# led_12led.net
KiCad netlist of a schematic drawn in EAGLE
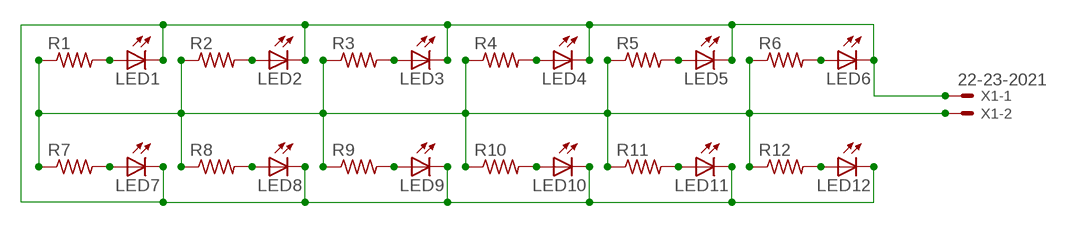
[diagram p0: schematic, sheet 1]

(export (version "E")
  (design (tool "Eeschema 10.0.6"))
  (components
    (comp (ref "LED1")
      (value "LED3MM")
      (footprint "eagle-import:LED3MM")
      (libsource (lib "eagle-import") (part "LED3MM"))
    )
    (comp (ref "LED2")
      (value "LED3MM")
      (footprint "eagle-import:LED3MM")
      (libsource (lib "eagle-import") (part "LED3MM"))
    )
    (comp (ref "LED3")
      (value "LED3MM")
      (footprint "eagle-import:LED3MM")
      (libsource (lib "eagle-import") (part "LED3MM"))
    )
    (comp (ref "LED4")
      (value "LED3MM")
      (footprint "eagle-import:LED3MM")
      (libsource (lib "eagle-import") (part "LED3MM"))
    )
    (comp (ref "LED5")
      (value "LED3MM")
      (footprint "eagle-import:LED3MM")
      (libsource (lib "eagle-import") (part "LED3MM"))
    )
    (comp (ref "LED6")
      (value "LED3MM")
      (footprint "eagle-import:LED3MM")
      (libsource (lib "eagle-import") (part "LED3MM"))
    )
    (comp (ref "LED7")
      (value "LED3MM")
      (footprint "eagle-import:LED3MM")
      (libsource (lib "eagle-import") (part "LED3MM"))
    )
    (comp (ref "LED8")
      (value "LED3MM")
      (footprint "eagle-import:LED3MM")
      (libsource (lib "eagle-import") (part "LED3MM"))
    )
    (comp (ref "LED9")
      (value "LED3MM")
      (footprint "eagle-import:LED3MM")
      (libsource (lib "eagle-import") (part "LED3MM"))
    )
    (comp (ref "LED10")
      (value "LED3MM")
      (footprint "eagle-import:LED3MM")
      (libsource (lib "eagle-import") (part "LED3MM"))
    )
    (comp (ref "LED11")
      (value "LED3MM")
      (footprint "eagle-import:LED3MM")
      (libsource (lib "eagle-import") (part "LED3MM"))
    )
    (comp (ref "LED12")
      (value "LED3MM")
      (footprint "eagle-import:LED3MM")
      (libsource (lib "eagle-import") (part "LED3MM"))
    )
    (comp (ref "R1")
      (value "R-US_0309/12")
      (footprint "eagle-import:0309_12")
      (libsource (lib "eagle-import") (part "R-US_0309/12"))
    )
    (comp (ref "R2")
      (value "R-US_0309/12")
      (footprint "eagle-import:0309_12")
      (libsource (lib "eagle-import") (part "R-US_0309/12"))
    )
    (comp (ref "R3")
      (value "R-US_0309/12")
      (footprint "eagle-import:0309_12")
      (libsource (lib "eagle-import") (part "R-US_0309/12"))
    )
    (comp (ref "R4")
      (value "R-US_0309/12")
      (footprint "eagle-import:0309_12")
      (libsource (lib "eagle-import") (part "R-US_0309/12"))
    )
    (comp (ref "R5")
      (value "R-US_0309/12")
      (footprint "eagle-import:0309_12")
      (libsource (lib "eagle-import") (part "R-US_0309/12"))
    )
    (comp (ref "R6")
      (value "R-US_0309/12")
      (footprint "eagle-import:0309_12")
      (libsource (lib "eagle-import") (part "R-US_0309/12"))
    )
    (comp (ref "R7")
      (value "R-US_0309/12")
      (footprint "eagle-import:0309_12")
      (libsource (lib "eagle-import") (part "R-US_0309/12"))
    )
    (comp (ref "R8")
      (value "R-US_0309/12")
      (footprint "eagle-import:0309_12")
      (libsource (lib "eagle-import") (part "R-US_0309/12"))
    )
    (comp (ref "R9")
      (value "R-US_0309/12")
      (footprint "eagle-import:0309_12")
      (libsource (lib "eagle-import") (part "R-US_0309/12"))
    )
    (comp (ref "R10")
      (value "R-US_0309/12")
      (footprint "eagle-import:0309_12")
      (libsource (lib "eagle-import") (part "R-US_0309/12"))
    )
    (comp (ref "R11")
      (value "R-US_0309/12")
      (footprint "eagle-import:0309_12")
      (libsource (lib "eagle-import") (part "R-US_0309/12"))
    )
    (comp (ref "R12")
      (value "R-US_0309/12")
      (footprint "eagle-import:0309_12")
      (libsource (lib "eagle-import") (part "R-US_0309/12"))
    )
    (comp (ref "X1")
      (value "22-23-2021")
      (footprint "eagle-import:22-23-2021")
      (fields (field (name "MF") "MOLEX"))
      (libsource (lib "eagle-import") (part "22-23-2021"))
    )
  )
  (nets
    (net (code "1") (name "Net-(LED1-C)") (class "Default")
      (node (ref "LED1") (pin "K") (pinfunction "C_K") (pintype "passive"))
      (node (ref "LED10") (pin "K") (pinfunction "C_K") (pintype "passive"))
      (node (ref "LED11") (pin "K") (pinfunction "C_K") (pintype "passive"))
      (node (ref "LED12") (pin "K") (pinfunction "C_K") (pintype "passive"))
      (node (ref "LED2") (pin "K") (pinfunction "C_K") (pintype "passive"))
      (node (ref "LED3") (pin "K") (pinfunction "C_K") (pintype "passive"))
      (node (ref "LED4") (pin "K") (pinfunction "C_K") (pintype "passive"))
      (node (ref "LED5") (pin "K") (pinfunction "C_K") (pintype "passive"))
      (node (ref "LED6") (pin "K") (pinfunction "C_K") (pintype "passive"))
      (node (ref "LED7") (pin "K") (pinfunction "C_K") (pintype "passive"))
      (node (ref "LED8") (pin "K") (pinfunction "C_K") (pintype "passive"))
      (node (ref "LED9") (pin "K") (pinfunction "C_K") (pintype "passive"))
      (node (ref "X1") (pin "1") (pinfunction "S_1") (pintype "passive"))
    )
    (net (code "2") (name "Net-(LED1-PadA)") (class "Default")
      (node (ref "LED1") (pin "A") (pinfunction "A_A") (pintype "passive"))
      (node (ref "R1") (pin "2") (pinfunction "2_2") (pintype "passive"))
    )
    (net (code "3") (name "Net-(LED2-PadA)") (class "Default")
      (node (ref "LED2") (pin "A") (pinfunction "A_A") (pintype "passive"))
      (node (ref "R2") (pin "2") (pinfunction "2_2") (pintype "passive"))
    )
    (net (code "4") (name "Net-(LED3-PadA)") (class "Default")
      (node (ref "LED3") (pin "A") (pinfunction "A_A") (pintype "passive"))
      (node (ref "R3") (pin "2") (pinfunction "2_2") (pintype "passive"))
    )
    (net (code "5") (name "Net-(LED4-PadA)") (class "Default")
      (node (ref "LED4") (pin "A") (pinfunction "A_A") (pintype "passive"))
      (node (ref "R4") (pin "2") (pinfunction "2_2") (pintype "passive"))
    )
    (net (code "6") (name "Net-(LED5-PadA)") (class "Default")
      (node (ref "LED5") (pin "A") (pinfunction "A_A") (pintype "passive"))
      (node (ref "R5") (pin "2") (pinfunction "2_2") (pintype "passive"))
    )
    (net (code "7") (name "Net-(LED6-PadA)") (class "Default")
      (node (ref "LED6") (pin "A") (pinfunction "A_A") (pintype "passive"))
      (node (ref "R6") (pin "2") (pinfunction "2_2") (pintype "passive"))
    )
    (net (code "8") (name "Net-(LED7-PadA)") (class "Default")
      (node (ref "LED7") (pin "A") (pinfunction "A_A") (pintype "passive"))
      (node (ref "R7") (pin "2") (pinfunction "2_2") (pintype "passive"))
    )
    (net (code "9") (name "Net-(LED8-PadA)") (class "Default")
      (node (ref "LED8") (pin "A") (pinfunction "A_A") (pintype "passive"))
      (node (ref "R8") (pin "2") (pinfunction "2_2") (pintype "passive"))
    )
    (net (code "10") (name "Net-(LED9-PadA)") (class "Default")
      (node (ref "LED9") (pin "A") (pinfunction "A_A") (pintype "passive"))
      (node (ref "R9") (pin "2") (pinfunction "2_2") (pintype "passive"))
    )
    (net (code "11") (name "Net-(LED10-PadA)") (class "Default")
      (node (ref "LED10") (pin "A") (pinfunction "A_A") (pintype "passive"))
      (node (ref "R10") (pin "2") (pinfunction "2_2") (pintype "passive"))
    )
    (net (code "12") (name "Net-(LED11-PadA)") (class "Default")
      (node (ref "LED11") (pin "A") (pinfunction "A_A") (pintype "passive"))
      (node (ref "R11") (pin "2") (pinfunction "2_2") (pintype "passive"))
    )
    (net (code "13") (name "Net-(LED12-PadA)") (class "Default")
      (node (ref "LED12") (pin "A") (pinfunction "A_A") (pintype "passive"))
      (node (ref "R12") (pin "2") (pinfunction "2_2") (pintype "passive"))
    )
    (net (code "14") (name "Net-(X1B-S)") (class "Default")
      (node (ref "R1") (pin "1") (pinfunction "1_1") (pintype "passive"))
      (node (ref "R10") (pin "1") (pinfunction "1_1") (pintype "passive"))
      (node (ref "R11") (pin "1") (pinfunction "1_1") (pintype "passive"))
      (node (ref "R12") (pin "1") (pinfunction "1_1") (pintype "passive"))
      (node (ref "R2") (pin "1") (pinfunction "1_1") (pintype "passive"))
      (node (ref "R3") (pin "1") (pinfunction "1_1") (pintype "passive"))
      (node (ref "R4") (pin "1") (pinfunction "1_1") (pintype "passive"))
      (node (ref "R5") (pin "1") (pinfunction "1_1") (pintype "passive"))
      (node (ref "R6") (pin "1") (pinfunction "1_1") (pintype "passive"))
      (node (ref "R7") (pin "1") (pinfunction "1_1") (pintype "passive"))
      (node (ref "R8") (pin "1") (pinfunction "1_1") (pintype "passive"))
      (node (ref "R9") (pin "1") (pinfunction "1_1") (pintype "passive"))
      (node (ref "X1") (pin "2") (pinfunction "S_2") (pintype "passive"))
    )
  )
)
